# Startgate_Controller-Motherboard.net
KiCad netlist of a schematic drawn in EAGLE
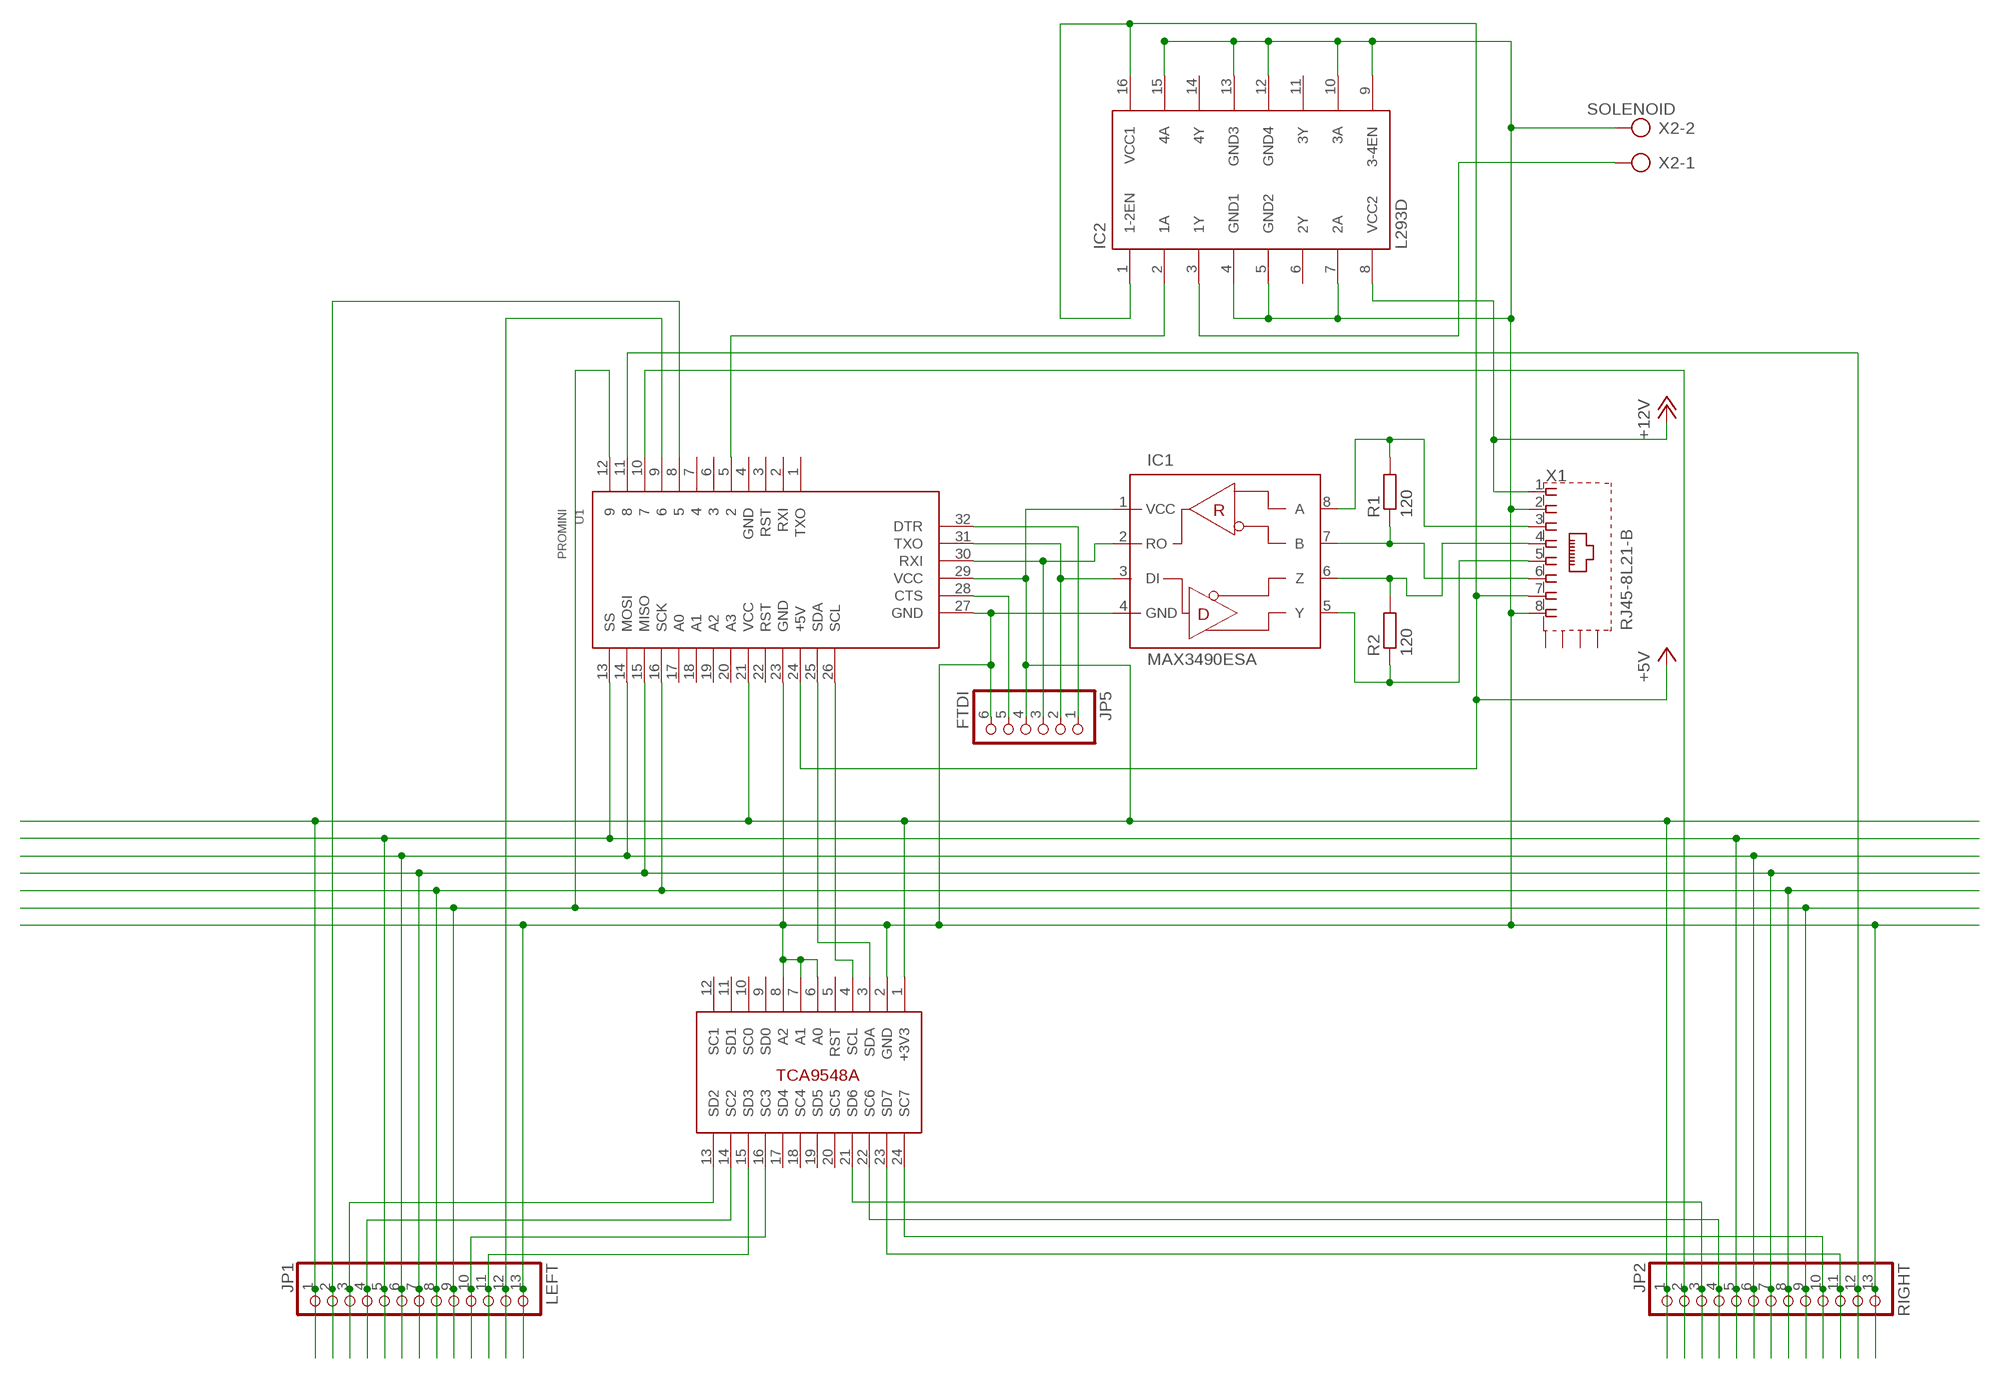
[diagram p0: schematic, sheet 1]

(export (version "E")
  (design (tool "Eeschema 10.0.6"))
  (components
    (comp (ref "IC1")
      (value "MAX3490ESA")
      (footprint "eagle-import:SO08")
      (libsource (lib "eagle-import") (part "MAX3490ESA"))
    )
    (comp (ref "IC2")
      (value "L293D")
      (footprint "eagle-import:DIL16")
      (libsource (lib "eagle-import") (part "L293D"))
    )
    (comp (ref "JP1")
      (value "LEFT")
      (footprint "eagle-import:1X13")
      (libsource (lib "eagle-import") (part "PINHD-1X13"))
    )
    (comp (ref "JP2")
      (value "RIGHT")
      (footprint "eagle-import:1X13")
      (libsource (lib "eagle-import") (part "PINHD-1X13"))
    )
    (comp (ref "JP5")
      (value "FTDI")
      (footprint "eagle-import:1X06")
      (libsource (lib "eagle-import") (part "PINHD-1X6"))
    )
    (comp (ref "R1")
      (value "120")
      (footprint "eagle-import:R0805")
      (libsource (lib "eagle-import") (part "R-EU_R0805"))
    )
    (comp (ref "R2")
      (value "120")
      (footprint "eagle-import:R0805")
      (libsource (lib "eagle-import") (part "R-EU_R0805"))
    )
    (comp (ref "U1")
      (value "PROMINI")
      (footprint "eagle-import:ARDUINOPROMINI")
      (libsource (lib "eagle-import") (part "ARDUINOPROMINI"))
    )
    (comp (ref "U2")
      (value "TCA9548A")
      (footprint "eagle-import:DIL24")
      (libsource (lib "eagle-import") (part "TCA9548A"))
    )
    (comp (ref "X1")
      (value "RJ45-8L21-B")
      (footprint "eagle-import:RJ45-SHIELD1")
      (libsource (lib "eagle-import") (part "RJ4521-B-8L"))
    )
    (comp (ref "X2")
      (value "SOLENOID")
      (footprint "eagle-import:AK300_2")
      (libsource (lib "eagle-import") (part "AK300/2"))
    )
  )
  (nets
    (net (code "1") (name "+5V") (class "Default")
      (node (ref "IC2") (pin "1") (pinfunction "1-2EN_1") (pintype "input"))
      (node (ref "IC2") (pin "16") (pinfunction "VCC1_16") (pintype "power_in"))
      (node (ref "U1") (pin "24") (pinfunction "+5V_24") (pintype "power_in"))
      (node (ref "X1") (pin "7") (pinfunction "7_7") (pintype "passive"))
    )
    (net (code "2") (name "+12V") (class "Default")
      (node (ref "IC2") (pin "8") (pinfunction "VCC2_8") (pintype "power_in"))
      (node (ref "X1") (pin "1") (pinfunction "1_1") (pintype "passive"))
    )
    (net (code "3") (name "Net-(IC1-A)") (class "Default")
      (node (ref "IC1") (pin "8") (pinfunction "A_8") (pintype "input"))
      (node (ref "R1") (pin "2") (pinfunction "2_2") (pintype "passive"))
      (node (ref "X1") (pin "3") (pinfunction "3_3") (pintype "passive"))
    )
    (net (code "4") (name "Net-(IC1-B)") (class "Default")
      (node (ref "IC1") (pin "7") (pinfunction "B_7") (pintype "input"))
      (node (ref "R1") (pin "1") (pinfunction "1_1") (pintype "passive"))
      (node (ref "X1") (pin "6") (pinfunction "6_6") (pintype "passive"))
    )
    (net (code "5") (name "Net-(IC1-DI)") (class "Default")
      (node (ref "IC1") (pin "3") (pinfunction "DI_3") (pintype "input"))
      (node (ref "JP5") (pin "2") (pinfunction "2_2") (pintype "passive"))
      (node (ref "U1") (pin "31") (pinfunction "TXO_31") (pintype "bidirectional"))
    )
    (net (code "6") (name "Net-(IC1-GND)") (class "Default")
      (node (ref "IC1") (pin "4") (pinfunction "GND_4") (pintype "power_in"))
      (node (ref "IC2") (pin "10") (pinfunction "3A_10") (pintype "input"))
      (node (ref "IC2") (pin "12") (pinfunction "GND4_12") (pintype "power_in"))
      (node (ref "IC2") (pin "13") (pinfunction "GND3_13") (pintype "power_in"))
      (node (ref "IC2") (pin "15") (pinfunction "4A_15") (pintype "input"))
      (node (ref "IC2") (pin "4") (pinfunction "GND1_4") (pintype "power_in"))
      (node (ref "IC2") (pin "5") (pinfunction "GND2_5") (pintype "power_in"))
      (node (ref "IC2") (pin "7") (pinfunction "2A_7") (pintype "input"))
      (node (ref "IC2") (pin "9") (pinfunction "3-4EN_9") (pintype "input"))
      (node (ref "JP1") (pin "13") (pinfunction "13_13") (pintype "passive"))
      (node (ref "JP2") (pin "13") (pinfunction "13_13") (pintype "passive"))
      (node (ref "JP5") (pin "6") (pinfunction "6_6") (pintype "passive"))
      (node (ref "U1") (pin "23") (pinfunction "GND_23") (pintype "bidirectional"))
      (node (ref "U1") (pin "27") (pinfunction "GND_27") (pintype "bidirectional"))
      (node (ref "U2") (pin "2") (pinfunction "GND_2") (pintype "power_in"))
      (node (ref "U2") (pin "6") (pinfunction "A0_6") (pintype "bidirectional"))
      (node (ref "U2") (pin "7") (pinfunction "A1_7") (pintype "bidirectional"))
      (node (ref "U2") (pin "8") (pinfunction "A2_8") (pintype "bidirectional"))
      (node (ref "X1") (pin "2") (pinfunction "2_2") (pintype "passive"))
      (node (ref "X1") (pin "8") (pinfunction "8_8") (pintype "passive"))
      (node (ref "X2") (pin "2") (pinfunction "KL_2") (pintype "passive"))
    )
    (net (code "7") (name "Net-(IC1-RO)") (class "Default")
      (node (ref "IC1") (pin "2") (pinfunction "RO_2") (pintype "output"))
      (node (ref "JP5") (pin "3") (pinfunction "3_3") (pintype "passive"))
      (node (ref "U1") (pin "30") (pinfunction "RXI_30") (pintype "bidirectional"))
    )
    (net (code "8") (name "Net-(IC1-VCC)") (class "Default")
      (node (ref "IC1") (pin "1") (pinfunction "VCC_1") (pintype "power_in"))
      (node (ref "JP1") (pin "1") (pinfunction "1_1") (pintype "passive"))
      (node (ref "JP2") (pin "1") (pinfunction "1_1") (pintype "passive"))
      (node (ref "JP5") (pin "4") (pinfunction "4_4") (pintype "passive"))
      (node (ref "U1") (pin "21") (pinfunction "VCC_21") (pintype "bidirectional"))
      (node (ref "U1") (pin "29") (pinfunction "VCC_29") (pintype "bidirectional"))
      (node (ref "U2") (pin "1") (pinfunction "+3V3_1") (pintype "power_in"))
    )
    (net (code "9") (name "Net-(IC1-Y)") (class "Default")
      (node (ref "IC1") (pin "5") (pinfunction "Y_5") (pintype "output"))
      (node (ref "R2") (pin "1") (pinfunction "1_1") (pintype "passive"))
      (node (ref "X1") (pin "5") (pinfunction "5_5") (pintype "passive"))
    )
    (net (code "10") (name "Net-(IC1-Z)") (class "Default")
      (node (ref "IC1") (pin "6") (pinfunction "Z_6") (pintype "output"))
      (node (ref "R2") (pin "2") (pinfunction "2_2") (pintype "passive"))
      (node (ref "X1") (pin "4") (pinfunction "4_4") (pintype "passive"))
    )
    (net (code "11") (name "Net-(IC2-1A)") (class "Default")
      (node (ref "IC2") (pin "2") (pinfunction "1A_2") (pintype "input"))
      (node (ref "U1") (pin "5") (pinfunction "2_5") (pintype "bidirectional"))
    )
    (net (code "12") (name "Net-(IC2-1Y)") (class "Default")
      (node (ref "IC2") (pin "3") (pinfunction "1Y_3") (pintype "output"))
      (node (ref "X2") (pin "1") (pinfunction "KL_1") (pintype "passive"))
    )
    (net (code "13") (name "Net-(U1-5)") (class "Default")
      (node (ref "JP1") (pin "2") (pinfunction "2_2") (pintype "passive"))
      (node (ref "U1") (pin "8") (pinfunction "5_8") (pintype "bidirectional"))
    )
    (net (code "14") (name "Net-(U1-6)") (class "Default")
      (node (ref "JP1") (pin "12") (pinfunction "12_12") (pintype "passive"))
      (node (ref "U1") (pin "9") (pinfunction "6_9") (pintype "bidirectional"))
    )
    (net (code "15") (name "Net-(U1-7)") (class "Default")
      (node (ref "JP2") (pin "2") (pinfunction "2_2") (pintype "passive"))
      (node (ref "U1") (pin "10") (pinfunction "7_10") (pintype "bidirectional"))
    )
    (net (code "16") (name "Net-(U1-8)") (class "Default")
      (node (ref "JP2") (pin "12") (pinfunction "12_12") (pintype "passive"))
      (node (ref "U1") (pin "11") (pinfunction "8_11") (pintype "bidirectional"))
    )
    (net (code "17") (name "Net-(U1-9)") (class "Default")
      (node (ref "JP1") (pin "9") (pinfunction "9_9") (pintype "passive"))
      (node (ref "JP2") (pin "9") (pinfunction "9_9") (pintype "passive"))
      (node (ref "U1") (pin "12") (pinfunction "9_12") (pintype "bidirectional"))
    )
    (net (code "18") (name "Net-(U1-CTS)") (class "Default")
      (node (ref "JP5") (pin "5") (pinfunction "5_5") (pintype "passive"))
      (node (ref "U1") (pin "28") (pinfunction "CTS_28") (pintype "bidirectional"))
    )
    (net (code "19") (name "Net-(U1-DTR)") (class "Default")
      (node (ref "JP5") (pin "1") (pinfunction "1_1") (pintype "passive"))
      (node (ref "U1") (pin "32") (pinfunction "DTR_32") (pintype "bidirectional"))
    )
    (net (code "20") (name "Net-(U1-MISO)") (class "Default")
      (node (ref "JP1") (pin "7") (pinfunction "7_7") (pintype "passive"))
      (node (ref "JP2") (pin "7") (pinfunction "7_7") (pintype "passive"))
      (node (ref "U1") (pin "15") (pinfunction "MISO_15") (pintype "bidirectional"))
    )
    (net (code "21") (name "Net-(U1-MOSI)") (class "Default")
      (node (ref "JP1") (pin "6") (pinfunction "6_6") (pintype "passive"))
      (node (ref "JP2") (pin "6") (pinfunction "6_6") (pintype "passive"))
      (node (ref "U1") (pin "14") (pinfunction "MOSI_14") (pintype "bidirectional"))
    )
    (net (code "22") (name "Net-(U1-SCK)") (class "Default")
      (node (ref "JP1") (pin "8") (pinfunction "8_8") (pintype "passive"))
      (node (ref "JP2") (pin "8") (pinfunction "8_8") (pintype "passive"))
      (node (ref "U1") (pin "16") (pinfunction "SCK_16") (pintype "bidirectional"))
    )
    (net (code "23") (name "Net-(U1-SCL)") (class "Default")
      (node (ref "U1") (pin "26") (pinfunction "SCL_26") (pintype "bidirectional"))
      (node (ref "U2") (pin "4") (pinfunction "SCL_4") (pintype "bidirectional"))
    )
    (net (code "24") (name "Net-(U1-SDA)") (class "Default")
      (node (ref "U1") (pin "25") (pinfunction "SDA_25") (pintype "bidirectional"))
      (node (ref "U2") (pin "3") (pinfunction "SDA_3") (pintype "bidirectional"))
    )
    (net (code "25") (name "Net-(U1-SS)") (class "Default")
      (node (ref "JP1") (pin "5") (pinfunction "5_5") (pintype "passive"))
      (node (ref "JP2") (pin "5") (pinfunction "5_5") (pintype "passive"))
      (node (ref "U1") (pin "13") (pinfunction "SS_13") (pintype "bidirectional"))
    )
    (net (code "26") (name "Net-(U2-SC2)") (class "Default")
      (node (ref "JP1") (pin "4") (pinfunction "4_4") (pintype "passive"))
      (node (ref "U2") (pin "14") (pinfunction "SC2_14") (pintype "bidirectional"))
    )
    (net (code "27") (name "Net-(U2-SC3)") (class "Default")
      (node (ref "JP1") (pin "10") (pinfunction "10_10") (pintype "passive"))
      (node (ref "U2") (pin "16") (pinfunction "SC3_16") (pintype "bidirectional"))
    )
    (net (code "28") (name "Net-(U2-SC6)") (class "Default")
      (node (ref "JP2") (pin "4") (pinfunction "4_4") (pintype "passive"))
      (node (ref "U2") (pin "22") (pinfunction "SC6_22") (pintype "bidirectional"))
    )
    (net (code "29") (name "Net-(U2-SC7)") (class "Default")
      (node (ref "JP2") (pin "10") (pinfunction "10_10") (pintype "passive"))
      (node (ref "U2") (pin "24") (pinfunction "SC7_24") (pintype "bidirectional"))
    )
    (net (code "30") (name "Net-(U2-SD2)") (class "Default")
      (node (ref "JP1") (pin "3") (pinfunction "3_3") (pintype "passive"))
      (node (ref "U2") (pin "13") (pinfunction "SD2_13") (pintype "bidirectional"))
    )
    (net (code "31") (name "Net-(U2-SD3)") (class "Default")
      (node (ref "JP1") (pin "11") (pinfunction "11_11") (pintype "passive"))
      (node (ref "U2") (pin "15") (pinfunction "SD3_15") (pintype "bidirectional"))
    )
    (net (code "32") (name "Net-(U2-SD6)") (class "Default")
      (node (ref "JP2") (pin "3") (pinfunction "3_3") (pintype "passive"))
      (node (ref "U2") (pin "21") (pinfunction "SD6_21") (pintype "bidirectional"))
    )
    (net (code "33") (name "Net-(U2-SD7)") (class "Default")
      (node (ref "JP2") (pin "11") (pinfunction "11_11") (pintype "passive"))
      (node (ref "U2") (pin "23") (pinfunction "SD7_23") (pintype "bidirectional"))
    )
    (net (code "34") (name "unconnected-(IC2-2Y-Pad6)") (class "Default")
      (node (ref "IC2") (pin "6") (pinfunction "2Y_6") (pintype "output"))
    )
    (net (code "35") (name "unconnected-(IC2-3Y-Pad11)") (class "Default")
      (node (ref "IC2") (pin "11") (pinfunction "3Y_11") (pintype "output"))
    )
    (net (code "36") (name "unconnected-(IC2-4Y-Pad14)") (class "Default")
      (node (ref "IC2") (pin "14") (pinfunction "4Y_14") (pintype "output"))
    )
    (net (code "37") (name "unconnected-(U1-3-Pad6)") (class "Default")
      (node (ref "U1") (pin "6") (pinfunction "3_6") (pintype "bidirectional"))
    )
    (net (code "38") (name "unconnected-(U1-4-Pad7)") (class "Default")
      (node (ref "U1") (pin "7") (pinfunction "4_7") (pintype "bidirectional"))
    )
    (net (code "39") (name "unconnected-(U1-A0-Pad17)") (class "Default")
      (node (ref "U1") (pin "17") (pinfunction "A0_17") (pintype "bidirectional"))
    )
    (net (code "40") (name "unconnected-(U1-A1-Pad18)") (class "Default")
      (node (ref "U1") (pin "18") (pinfunction "A1_18") (pintype "bidirectional"))
    )
    (net (code "41") (name "unconnected-(U1-A2-Pad19)") (class "Default")
      (node (ref "U1") (pin "19") (pinfunction "A2_19") (pintype "bidirectional"))
    )
    (net (code "42") (name "unconnected-(U1-A3-Pad20)") (class "Default")
      (node (ref "U1") (pin "20") (pinfunction "A3_20") (pintype "bidirectional"))
    )
    (net (code "43") (name "unconnected-(U1-GND-Pad4)") (class "Default")
      (node (ref "U1") (pin "4") (pinfunction "GND_4") (pintype "bidirectional"))
    )
    (net (code "44") (name "unconnected-(U1-RST-Pad3)") (class "Default")
      (node (ref "U1") (pin "3") (pinfunction "RST_3") (pintype "bidirectional"))
    )
    (net (code "45") (name "unconnected-(U1-RST-Pad22)") (class "Default")
      (node (ref "U1") (pin "22") (pinfunction "RST_22") (pintype "bidirectional"))
    )
    (net (code "46") (name "unconnected-(U1-RXI-Pad2)") (class "Default")
      (node (ref "U1") (pin "2") (pinfunction "RXI_2") (pintype "bidirectional"))
    )
    (net (code "47") (name "unconnected-(U1-TXO-Pad1)") (class "Default")
      (node (ref "U1") (pin "1") (pinfunction "TXO_1") (pintype "bidirectional"))
    )
    (net (code "48") (name "unconnected-(U2-RST-Pad5)") (class "Default")
      (node (ref "U2") (pin "5") (pinfunction "RST_5") (pintype "bidirectional"))
    )
    (net (code "49") (name "unconnected-(U2-SC0-Pad10)") (class "Default")
      (node (ref "U2") (pin "10") (pinfunction "SC0_10") (pintype "bidirectional"))
    )
    (net (code "50") (name "unconnected-(U2-SC1-Pad12)") (class "Default")
      (node (ref "U2") (pin "12") (pinfunction "SC1_12") (pintype "bidirectional"))
    )
    (net (code "51") (name "unconnected-(U2-SC4-Pad18)") (class "Default")
      (node (ref "U2") (pin "18") (pinfunction "SC4_18") (pintype "bidirectional"))
    )
    (net (code "52") (name "unconnected-(U2-SC5-Pad20)") (class "Default")
      (node (ref "U2") (pin "20") (pinfunction "SC5_20") (pintype "bidirectional"))
    )
    (net (code "53") (name "unconnected-(U2-SD0-Pad9)") (class "Default")
      (node (ref "U2") (pin "9") (pinfunction "SD0_9") (pintype "bidirectional"))
    )
    (net (code "54") (name "unconnected-(U2-SD1-Pad11)") (class "Default")
      (node (ref "U2") (pin "11") (pinfunction "SD1_11") (pintype "bidirectional"))
    )
    (net (code "55") (name "unconnected-(U2-SD4-Pad17)") (class "Default")
      (node (ref "U2") (pin "17") (pinfunction "SD4_17") (pintype "bidirectional"))
    )
    (net (code "56") (name "unconnected-(U2-SD5-Pad19)") (class "Default")
      (node (ref "U2") (pin "19") (pinfunction "SD5_19") (pintype "bidirectional"))
    )
    (net (code "57") (name "unconnected-(X1-S-PadS1)") (class "Default")
      (node (ref "X1") (pin "S1") (pinfunction "S_S1") (pintype "passive"))
    )
    (net (code "58") (name "unconnected-(X1-S-PadS2)") (class "Default")
      (node (ref "X1") (pin "S2") (pinfunction "S_S2") (pintype "passive"))
    )
    (net (code "59") (name "unconnected-(X1-S-PadS3)") (class "Default")
      (node (ref "X1") (pin "S3") (pinfunction "S_S3") (pintype "passive"))
    )
    (net (code "60") (name "unconnected-(X1-S-PadS4)") (class "Default")
      (node (ref "X1") (pin "S4") (pinfunction "S_S4") (pintype "passive"))
    )
  )
)
